# preamp.net
KiCad netlist of a schematic drawn in Altium Designer
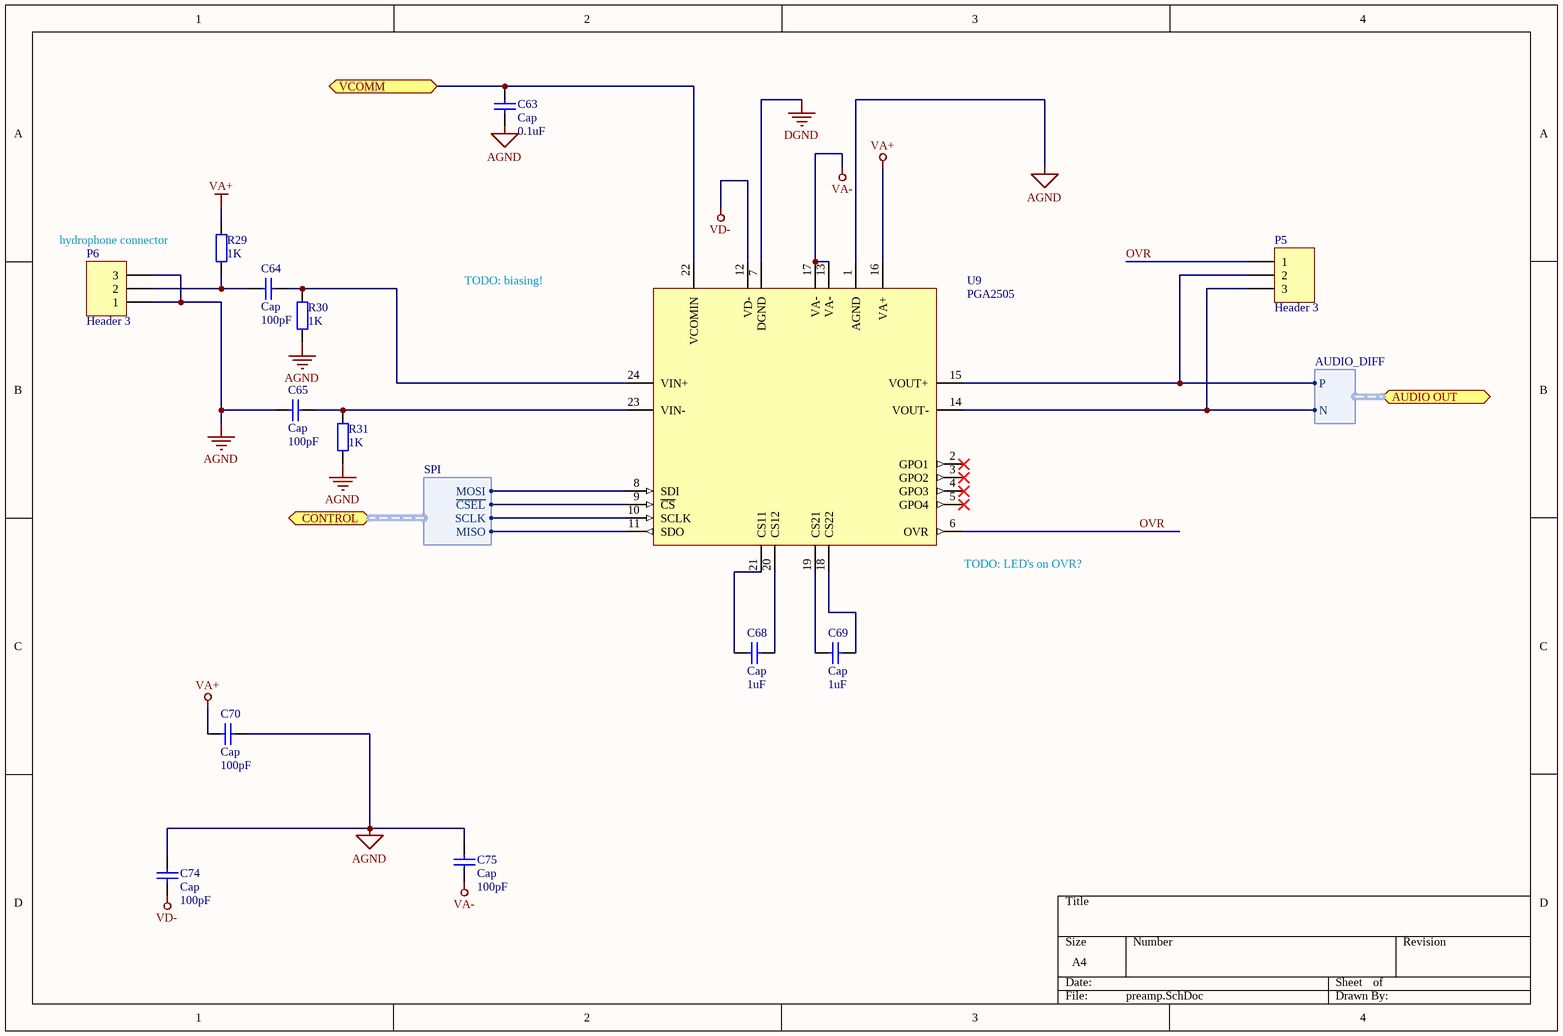
[diagram p0: preamp.SchDoc]

(export (version "E")
  (design (tool "Eeschema 10.0.6"))
  (components
    (comp (ref "C63")
      (value "Cap")
      (footprint "C0603")
      (description "Capacitor")
      (fields (field (name "ALTIUM_VALUE") "0.1uF") (field (name "PUBLISHER") "Altium Limited"))
      (libsource (lib "Miscellaneous Devices") (part "Cap"))
    )
    (comp (ref "C64")
      (value "Cap")
      (footprint "C0603")
      (description "Capacitor")
      (fields (field (name "ALTIUM_VALUE") "100pF") (field (name "PUBLISHER") "Altium Limited"))
      (libsource (lib "Miscellaneous Devices") (part "Cap"))
    )
    (comp (ref "C65")
      (value "Cap")
      (footprint "C0603")
      (description "Capacitor")
      (fields (field (name "ALTIUM_VALUE") "100pF") (field (name "PUBLISHER") "Altium Limited"))
      (libsource (lib "Miscellaneous Devices") (part "Cap"))
    )
    (comp (ref "C68")
      (value "Cap")
      (footprint "C0603")
      (description "Capacitor")
      (fields (field (name "ALTIUM_VALUE") "1uF") (field (name "PUBLISHER") "Altium Limited"))
      (libsource (lib "Miscellaneous Devices") (part "Cap"))
    )
    (comp (ref "C69")
      (value "Cap")
      (footprint "C0603")
      (description "Capacitor")
      (fields (field (name "ALTIUM_VALUE") "1uF") (field (name "PUBLISHER") "Altium Limited"))
      (libsource (lib "Miscellaneous Devices") (part "Cap"))
    )
    (comp (ref "C70")
      (value "Cap")
      (footprint "C0603")
      (description "Capacitor")
      (fields (field (name "ALTIUM_VALUE") "100pF") (field (name "PUBLISHER") "Altium Limited"))
      (libsource (lib "Miscellaneous Devices") (part "Cap"))
    )
    (comp (ref "C74")
      (value "Cap")
      (footprint "C0603")
      (description "Capacitor")
      (fields (field (name "ALTIUM_VALUE") "100pF") (field (name "PUBLISHER") "Altium Limited"))
      (libsource (lib "") (part "Cap_1"))
    )
    (comp (ref "C75")
      (value "Cap")
      (footprint "C0603")
      (description "Capacitor")
      (fields (field (name "ALTIUM_VALUE") "100pF") (field (name "PUBLISHER") "Altium Limited"))
      (libsource (lib "Miscellaneous Devices") (part "Cap"))
    )
    (comp (ref "P5")
      (value "Header 3")
      (footprint "HDR1X3")
      (description "Header, 3-Pin")
      (fields (field (name "PUBLISHER") "Altium Limited"))
      (libsource (lib "") (part "Header 3_1"))
    )
    (comp (ref "P6")
      (value "Header 3")
      (footprint "S03B-PASK-2")
      (description "Header, 3-Pin")
      (fields (field (name "PUBLISHER") "Altium Limited"))
      (libsource (lib "Miscellaneous Connectors") (part "Header 3"))
    )
    (comp (ref "R29")
      (value "1K")
      (footprint "R0603")
      (description "Resistor")
      (fields (field (name "Comment") "Res2") (field (name "PUBLISHER") "Altium Limited"))
      (libsource (lib "Miscellaneous Devices") (part "Res2"))
    )
    (comp (ref "R30")
      (value "1K")
      (footprint "R0603")
      (description "Resistor")
      (fields (field (name "Comment") "Res2") (field (name "PUBLISHER") "Altium Limited"))
      (libsource (lib "Miscellaneous Devices") (part "Res2"))
    )
    (comp (ref "R31")
      (value "1K")
      (footprint "R0603")
      (description "Resistor")
      (fields (field (name "Comment") "Res2") (field (name "PUBLISHER") "Altium Limited"))
      (libsource (lib "Miscellaneous Devices") (part "Res2"))
    )
    (comp (ref "U9")
      (value "PGA2505")
      (footprint "SOP65P780X200-24N")
      (description "IC, MICROPHONE AMP, 24TSSOP")
      (libsource (lib "PGA2505") (part "PGA2505"))
    )
  )
  (nets
    (net (code "3") (name "/MISO") (class "Default")
      (node (ref "U9") (pin "11") (pinfunction "SDO_11") (pintype "output"))
    )
    (net (code "4") (name "/MOSI") (class "Default")
      (node (ref "U9") (pin "8") (pinfunction "SDI_8") (pintype "input"))
    )
    (net (code "5") (name "/N") (class "Default")
      (node (ref "P5") (pin "3") (pinfunction "3_3") (pintype "passive"))
      (node (ref "U9") (pin "14") (pinfunction "VOUT-_14") (pintype "passive"))
    )
    (net (code "6") (name "/OVR") (class "Default")
      (node (ref "P5") (pin "1") (pinfunction "1_1") (pintype "passive"))
      (node (ref "U9") (pin "6") (pinfunction "OVR_6") (pintype "output"))
    )
    (net (code "7") (name "/P") (class "Default")
      (node (ref "P5") (pin "2") (pinfunction "2_2") (pintype "passive"))
      (node (ref "U9") (pin "15") (pinfunction "VOUT+_15") (pintype "passive"))
    )
    (net (code "8") (name "/SCLK") (class "Default")
      (node (ref "U9") (pin "10") (pinfunction "SCLK_10") (pintype "input"))
    )
    (net (code "9") (name "/VCOMM") (class "Default")
      (node (ref "C63") (pin "2") (pinfunction "2_2") (pintype "passive"))
      (node (ref "U9") (pin "22") (pinfunction "VCOMIN_22") (pintype "power_in"))
    )
    (net (code "12") (name "/~{CSEL}") (class "Default")
      (node (ref "U9") (pin "9") (pinfunction "~{CS}_9") (pintype "input"))
    )
    (net (code "13") (name "AGND") (class "Default")
      (node (ref "C63") (pin "1") (pinfunction "1_1") (pintype "passive"))
      (node (ref "C65") (pin "2") (pinfunction "2_2") (pintype "passive"))
      (node (ref "C70") (pin "2") (pinfunction "2_2") (pintype "passive"))
      (node (ref "C74") (pin "2") (pinfunction "2_2") (pintype "passive"))
      (node (ref "C75") (pin "2") (pinfunction "2_2") (pintype "passive"))
      (node (ref "P6") (pin "1") (pinfunction "1_1") (pintype "passive"))
      (node (ref "P6") (pin "3") (pinfunction "3_3") (pintype "passive"))
      (node (ref "R30") (pin "1") (pinfunction "1_1") (pintype "passive"))
      (node (ref "R31") (pin "1") (pinfunction "1_1") (pintype "passive"))
      (node (ref "U9") (pin "1") (pinfunction "AGND_1") (pintype "power_in"))
    )
    (net (code "14") (name "DGND") (class "Default")
      (node (ref "U9") (pin "7") (pinfunction "DGND_7") (pintype "power_in"))
    )
    (net (code "15") (name "Net-(C64-Pad2)") (class "Default")
      (node (ref "C64") (pin "2") (pinfunction "2_2") (pintype "passive"))
      (node (ref "P6") (pin "2") (pinfunction "2_2") (pintype "passive"))
      (node (ref "R29") (pin "1") (pinfunction "1_1") (pintype "passive"))
    )
    (net (code "16") (name "Net-(U9-CS11)") (class "Default")
      (node (ref "C68") (pin "1") (pinfunction "1_1") (pintype "passive"))
      (node (ref "U9") (pin "21") (pinfunction "CS11_21") (pintype "passive"))
    )
    (net (code "17") (name "Net-(U9-CS12)") (class "Default")
      (node (ref "C68") (pin "2") (pinfunction "2_2") (pintype "passive"))
      (node (ref "U9") (pin "20") (pinfunction "CS12_20") (pintype "passive"))
    )
    (net (code "18") (name "Net-(U9-CS21)") (class "Default")
      (node (ref "C69") (pin "1") (pinfunction "1_1") (pintype "passive"))
      (node (ref "U9") (pin "19") (pinfunction "CS21_19") (pintype "passive"))
    )
    (net (code "19") (name "Net-(U9-CS22)") (class "Default")
      (node (ref "C69") (pin "2") (pinfunction "2_2") (pintype "passive"))
      (node (ref "U9") (pin "18") (pinfunction "CS22_18") (pintype "passive"))
    )
    (net (code "20") (name "Net-(U9-VIN+)") (class "Default")
      (node (ref "C64") (pin "1") (pinfunction "1_1") (pintype "passive"))
      (node (ref "R30") (pin "2") (pinfunction "2_2") (pintype "passive"))
      (node (ref "U9") (pin "24") (pinfunction "VIN+_24") (pintype "passive"))
    )
    (net (code "21") (name "Net-(U9-VIN-)") (class "Default")
      (node (ref "C65") (pin "1") (pinfunction "1_1") (pintype "passive"))
      (node (ref "R31") (pin "2") (pinfunction "2_2") (pintype "passive"))
      (node (ref "U9") (pin "23") (pinfunction "VIN-_23") (pintype "passive"))
    )
    (net (code "22") (name "VA+") (class "Default")
      (node (ref "C70") (pin "1") (pinfunction "1_1") (pintype "passive"))
      (node (ref "R29") (pin "2") (pinfunction "2_2") (pintype "passive"))
      (node (ref "U9") (pin "16") (pinfunction "VA+_16") (pintype "power_in"))
    )
    (net (code "23") (name "VA-") (class "Default")
      (node (ref "C75") (pin "1") (pinfunction "1_1") (pintype "passive"))
      (node (ref "U9") (pin "13") (pinfunction "VA-_13") (pintype "power_in"))
      (node (ref "U9") (pin "17") (pinfunction "VA-_17") (pintype "power_in"))
    )
    (net (code "24") (name "VD-") (class "Default")
      (node (ref "C74") (pin "1") (pinfunction "1_1") (pintype "passive"))
      (node (ref "U9") (pin "12") (pinfunction "VD-_12") (pintype "power_in"))
    )
    (net (code "25") (name "unconnected-(U9-GPO1-Pad2)") (class "Default")
      (node (ref "U9") (pin "2") (pinfunction "GPO1_2") (pintype "output+no_connect"))
    )
    (net (code "26") (name "unconnected-(U9-GPO2-Pad3)") (class "Default")
      (node (ref "U9") (pin "3") (pinfunction "GPO2_3") (pintype "output+no_connect"))
    )
    (net (code "27") (name "unconnected-(U9-GPO3-Pad4)") (class "Default")
      (node (ref "U9") (pin "4") (pinfunction "GPO3_4") (pintype "output+no_connect"))
    )
    (net (code "28") (name "unconnected-(U9-GPO4-Pad5)") (class "Default")
      (node (ref "U9") (pin "5") (pinfunction "GPO4_5") (pintype "output+no_connect"))
    )
  )
)
